# main_schematic.net
KiCad netlist of a schematic drawn in EAGLE
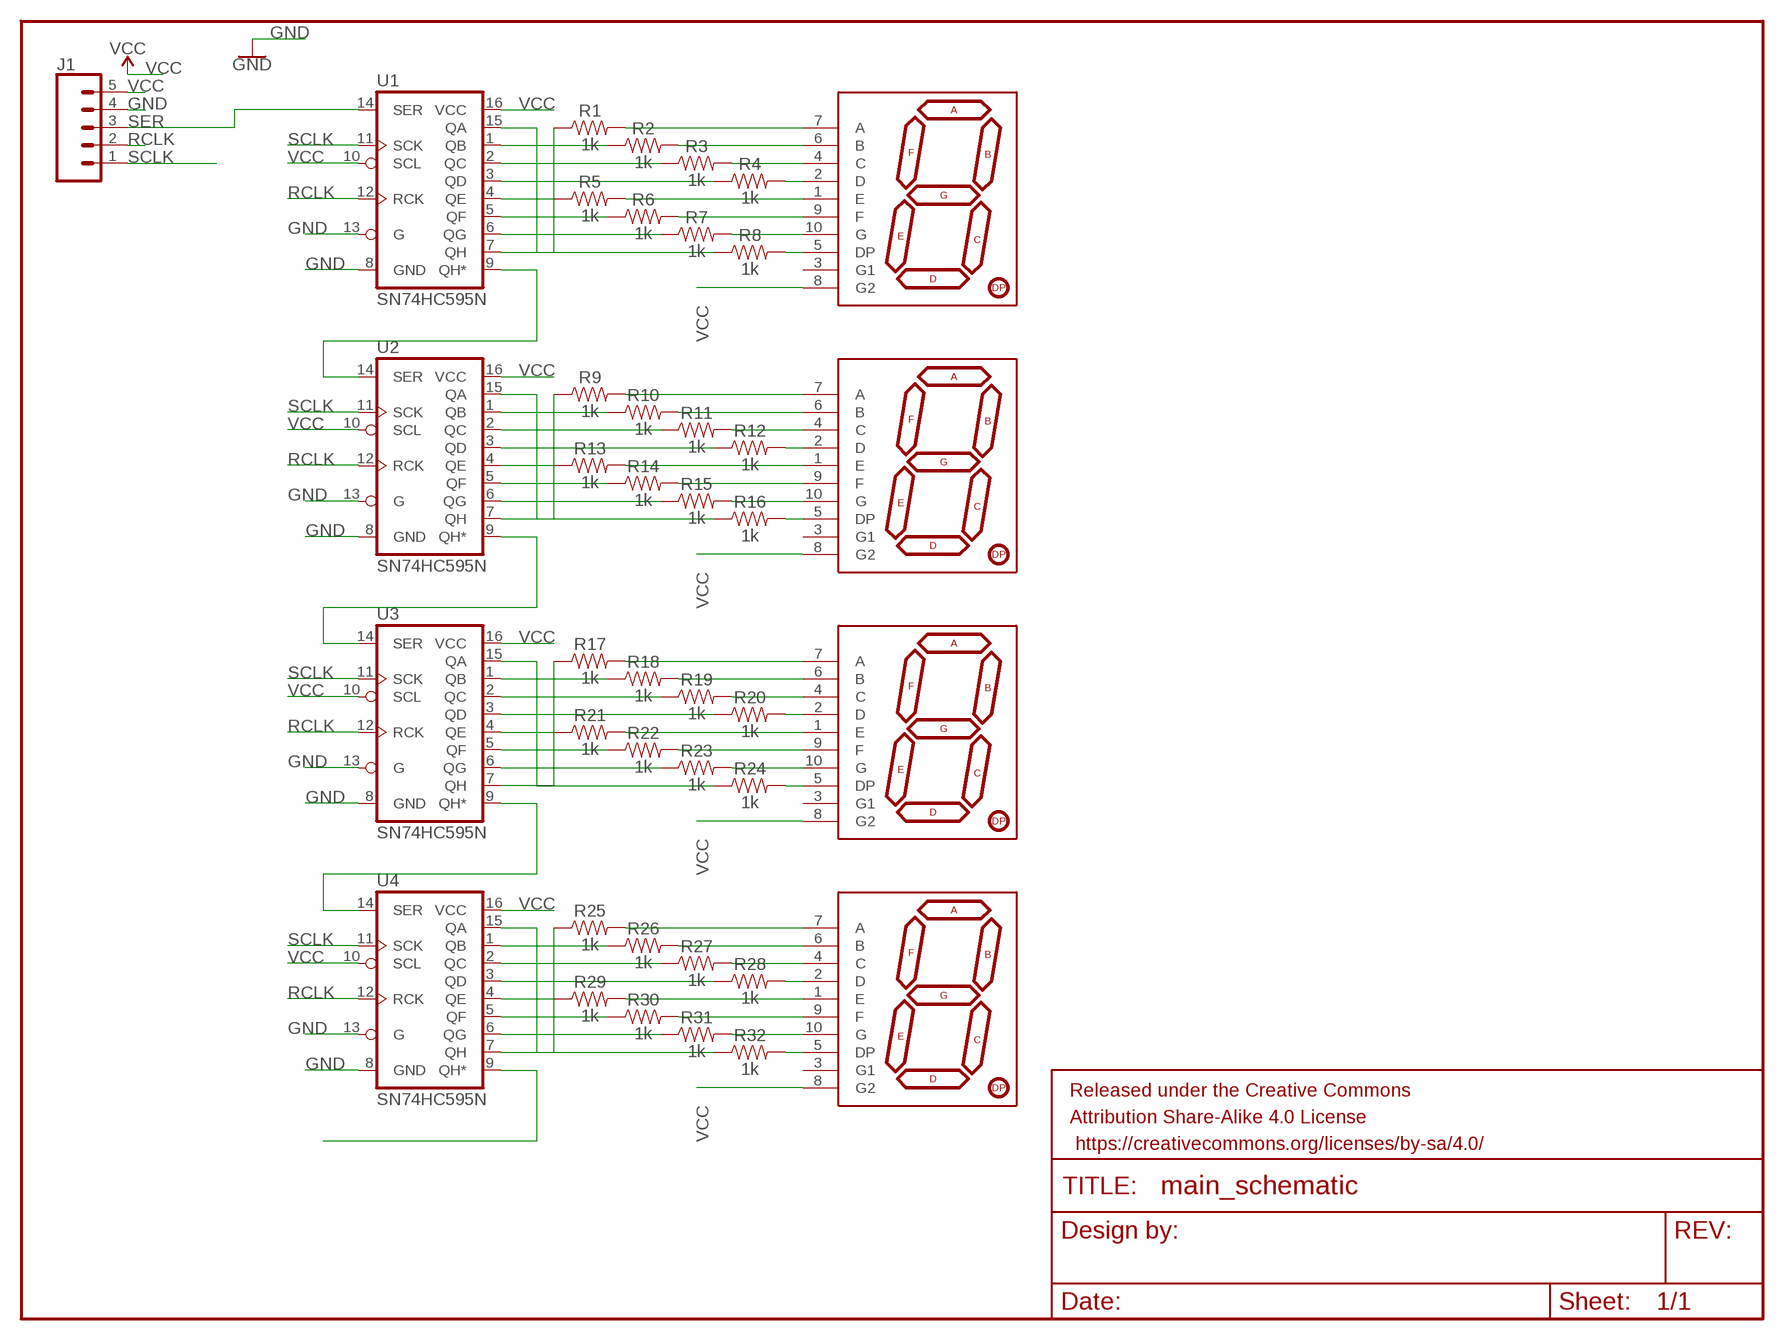
[diagram p0: schematic, sheet 1]

(export (version "E")
  (design (tool "Eeschema 10.0.6"))
  (components
    (comp (ref "FRAME1")
      (value "FRAME-LETTER")
      (footprint "eagle-import:CREATIVE_COMMONS")
      (libsource (lib "eagle-import") (part "FRAME-LETTER"))
    )
    (comp (ref "J1")
      (value "CONN_05")
      (footprint "eagle-import:1X05")
      (libsource (lib "eagle-import") (part "CONN_05"))
    )
    (comp (ref "R1")
      (value "1k")
      (footprint "eagle-import:AXIAL-0.3-KIT")
      (libsource (lib "eagle-import") (part "1KOHM-HORIZ_KIT-1/4W-5%"))
    )
    (comp (ref "R2")
      (value "1k")
      (footprint "eagle-import:AXIAL-0.3-KIT")
      (libsource (lib "eagle-import") (part "1KOHM-HORIZ_KIT-1/4W-5%"))
    )
    (comp (ref "R3")
      (value "1k")
      (footprint "eagle-import:AXIAL-0.3-KIT")
      (libsource (lib "eagle-import") (part "1KOHM-HORIZ_KIT-1/4W-5%"))
    )
    (comp (ref "R4")
      (value "1k")
      (footprint "eagle-import:AXIAL-0.3-KIT")
      (libsource (lib "eagle-import") (part "1KOHM-HORIZ_KIT-1/4W-5%"))
    )
    (comp (ref "R5")
      (value "1k")
      (footprint "eagle-import:AXIAL-0.3-KIT")
      (libsource (lib "eagle-import") (part "1KOHM-HORIZ_KIT-1/4W-5%"))
    )
    (comp (ref "R6")
      (value "1k")
      (footprint "eagle-import:AXIAL-0.3-KIT")
      (libsource (lib "eagle-import") (part "1KOHM-HORIZ_KIT-1/4W-5%"))
    )
    (comp (ref "R7")
      (value "1k")
      (footprint "eagle-import:AXIAL-0.3-KIT")
      (libsource (lib "eagle-import") (part "1KOHM-HORIZ_KIT-1/4W-5%"))
    )
    (comp (ref "R8")
      (value "1k")
      (footprint "eagle-import:AXIAL-0.3-KIT")
      (libsource (lib "eagle-import") (part "1KOHM-HORIZ_KIT-1/4W-5%"))
    )
    (comp (ref "R9")
      (value "1k")
      (footprint "eagle-import:AXIAL-0.3-KIT")
      (libsource (lib "eagle-import") (part "1KOHM-HORIZ_KIT-1/4W-5%"))
    )
    (comp (ref "R10")
      (value "1k")
      (footprint "eagle-import:AXIAL-0.3-KIT")
      (libsource (lib "eagle-import") (part "1KOHM-HORIZ_KIT-1/4W-5%"))
    )
    (comp (ref "R11")
      (value "1k")
      (footprint "eagle-import:AXIAL-0.3-KIT")
      (libsource (lib "eagle-import") (part "1KOHM-HORIZ_KIT-1/4W-5%"))
    )
    (comp (ref "R12")
      (value "1k")
      (footprint "eagle-import:AXIAL-0.3-KIT")
      (libsource (lib "eagle-import") (part "1KOHM-HORIZ_KIT-1/4W-5%"))
    )
    (comp (ref "R13")
      (value "1k")
      (footprint "eagle-import:AXIAL-0.3-KIT")
      (libsource (lib "eagle-import") (part "1KOHM-HORIZ_KIT-1/4W-5%"))
    )
    (comp (ref "R14")
      (value "1k")
      (footprint "eagle-import:AXIAL-0.3-KIT")
      (libsource (lib "eagle-import") (part "1KOHM-HORIZ_KIT-1/4W-5%"))
    )
    (comp (ref "R15")
      (value "1k")
      (footprint "eagle-import:AXIAL-0.3-KIT")
      (libsource (lib "eagle-import") (part "1KOHM-HORIZ_KIT-1/4W-5%"))
    )
    (comp (ref "R16")
      (value "1k")
      (footprint "eagle-import:AXIAL-0.3-KIT")
      (libsource (lib "eagle-import") (part "1KOHM-HORIZ_KIT-1/4W-5%"))
    )
    (comp (ref "R17")
      (value "1k")
      (footprint "eagle-import:AXIAL-0.3-KIT")
      (libsource (lib "eagle-import") (part "1KOHM-HORIZ_KIT-1/4W-5%"))
    )
    (comp (ref "R18")
      (value "1k")
      (footprint "eagle-import:AXIAL-0.3-KIT")
      (libsource (lib "eagle-import") (part "1KOHM-HORIZ_KIT-1/4W-5%"))
    )
    (comp (ref "R19")
      (value "1k")
      (footprint "eagle-import:AXIAL-0.3-KIT")
      (libsource (lib "eagle-import") (part "1KOHM-HORIZ_KIT-1/4W-5%"))
    )
    (comp (ref "R20")
      (value "1k")
      (footprint "eagle-import:AXIAL-0.3-KIT")
      (libsource (lib "eagle-import") (part "1KOHM-HORIZ_KIT-1/4W-5%"))
    )
    (comp (ref "R21")
      (value "1k")
      (footprint "eagle-import:AXIAL-0.3-KIT")
      (libsource (lib "eagle-import") (part "1KOHM-HORIZ_KIT-1/4W-5%"))
    )
    (comp (ref "R22")
      (value "1k")
      (footprint "eagle-import:AXIAL-0.3-KIT")
      (libsource (lib "eagle-import") (part "1KOHM-HORIZ_KIT-1/4W-5%"))
    )
    (comp (ref "R23")
      (value "1k")
      (footprint "eagle-import:AXIAL-0.3-KIT")
      (libsource (lib "eagle-import") (part "1KOHM-HORIZ_KIT-1/4W-5%"))
    )
    (comp (ref "R24")
      (value "1k")
      (footprint "eagle-import:AXIAL-0.3-KIT")
      (libsource (lib "eagle-import") (part "1KOHM-HORIZ_KIT-1/4W-5%"))
    )
    (comp (ref "R25")
      (value "1k")
      (footprint "eagle-import:AXIAL-0.3-KIT")
      (libsource (lib "eagle-import") (part "1KOHM-HORIZ_KIT-1/4W-5%"))
    )
    (comp (ref "R26")
      (value "1k")
      (footprint "eagle-import:AXIAL-0.3-KIT")
      (libsource (lib "eagle-import") (part "1KOHM-HORIZ_KIT-1/4W-5%"))
    )
    (comp (ref "R27")
      (value "1k")
      (footprint "eagle-import:AXIAL-0.3-KIT")
      (libsource (lib "eagle-import") (part "1KOHM-HORIZ_KIT-1/4W-5%"))
    )
    (comp (ref "R28")
      (value "1k")
      (footprint "eagle-import:AXIAL-0.3-KIT")
      (libsource (lib "eagle-import") (part "1KOHM-HORIZ_KIT-1/4W-5%"))
    )
    (comp (ref "R29")
      (value "1k")
      (footprint "eagle-import:AXIAL-0.3-KIT")
      (libsource (lib "eagle-import") (part "1KOHM-HORIZ_KIT-1/4W-5%"))
    )
    (comp (ref "R30")
      (value "1k")
      (footprint "eagle-import:AXIAL-0.3-KIT")
      (libsource (lib "eagle-import") (part "1KOHM-HORIZ_KIT-1/4W-5%"))
    )
    (comp (ref "R31")
      (value "1k")
      (footprint "eagle-import:AXIAL-0.3-KIT")
      (libsource (lib "eagle-import") (part "1KOHM-HORIZ_KIT-1/4W-5%"))
    )
    (comp (ref "R32")
      (value "1k")
      (footprint "eagle-import:AXIAL-0.3-KIT")
      (libsource (lib "eagle-import") (part "1KOHM-HORIZ_KIT-1/4W-5%"))
    )
    (comp (ref "U$1")
      (value "YSD-160AB3C-8")
      (footprint "eagle-import:7-SEGMENT-1_PTH-EZ")
      (libsource (lib "eagle-import") (part "7-SEGMENT-1DIGIT-1INCH-BLUE-EZ"))
    )
    (comp (ref "U$2")
      (value "YSD-160AB3C-8")
      (footprint "eagle-import:7-SEGMENT-1_PTH-EZ")
      (libsource (lib "eagle-import") (part "7-SEGMENT-1DIGIT-1INCH-BLUE-EZ"))
    )
    (comp (ref "U$3")
      (value "YSD-160AB3C-8")
      (footprint "eagle-import:7-SEGMENT-1_PTH-EZ")
      (libsource (lib "eagle-import") (part "7-SEGMENT-1DIGIT-1INCH-BLUE-EZ"))
    )
    (comp (ref "U$4")
      (value "YSD-160AB3C-8")
      (footprint "eagle-import:7-SEGMENT-1_PTH-EZ")
      (libsource (lib "eagle-import") (part "7-SEGMENT-1DIGIT-1INCH-BLUE-EZ"))
    )
    (comp (ref "U1")
      (value "SN74HC595N")
      (footprint "eagle-import:DIP16")
      (libsource (lib "eagle-import") (part "74595NHC"))
    )
    (comp (ref "U2")
      (value "SN74HC595N")
      (footprint "eagle-import:DIP16")
      (libsource (lib "eagle-import") (part "74595NHC"))
    )
    (comp (ref "U3")
      (value "SN74HC595N")
      (footprint "eagle-import:DIP16")
      (libsource (lib "eagle-import") (part "74595NHC"))
    )
    (comp (ref "U4")
      (value "SN74HC595N")
      (footprint "eagle-import:DIP16")
      (libsource (lib "eagle-import") (part "74595NHC"))
    )
  )
  (nets
    (net (code "1") (name "/RCLK") (class "Default")
      (node (ref "J1") (pin "2") (pinfunction "2_2") (pintype "passive"))
      (node (ref "U1") (pin "12") (pinfunction "RCK_12") (pintype "input"))
      (node (ref "U2") (pin "12") (pinfunction "RCK_12") (pintype "input"))
      (node (ref "U3") (pin "12") (pinfunction "RCK_12") (pintype "input"))
      (node (ref "U4") (pin "12") (pinfunction "RCK_12") (pintype "input"))
    )
    (net (code "2") (name "/SCLK") (class "Default")
      (node (ref "J1") (pin "1") (pinfunction "1_1") (pintype "passive"))
      (node (ref "U1") (pin "11") (pinfunction "SCK_11") (pintype "input"))
      (node (ref "U2") (pin "11") (pinfunction "SCK_11") (pintype "input"))
      (node (ref "U3") (pin "11") (pinfunction "SCK_11") (pintype "input"))
      (node (ref "U4") (pin "11") (pinfunction "SCK_11") (pintype "input"))
    )
    (net (code "3") (name "/SER") (class "Default")
      (node (ref "J1") (pin "3") (pinfunction "3_3") (pintype "passive"))
      (node (ref "U1") (pin "14") (pinfunction "SER_14") (pintype "input"))
    )
    (net (code "4") (name "GND") (class "Default")
      (node (ref "J1") (pin "4") (pinfunction "4_4") (pintype "passive"))
      (node (ref "U1") (pin "13") (pinfunction "G_13") (pintype "input"))
      (node (ref "U1") (pin "8") (pinfunction "GND_8") (pintype "power_in"))
      (node (ref "U2") (pin "13") (pinfunction "G_13") (pintype "input"))
      (node (ref "U2") (pin "8") (pinfunction "GND_8") (pintype "power_in"))
      (node (ref "U3") (pin "13") (pinfunction "G_13") (pintype "input"))
      (node (ref "U3") (pin "8") (pinfunction "GND_8") (pintype "power_in"))
      (node (ref "U4") (pin "13") (pinfunction "G_13") (pintype "input"))
      (node (ref "U4") (pin "8") (pinfunction "GND_8") (pintype "power_in"))
    )
    (net (code "5") (name "Net-(R1-1)") (class "Default")
      (node (ref "R1") (pin "P$1") (pinfunction "1_P$1") (pintype "passive"))
      (node (ref "U1") (pin "7") (pinfunction "QH_7") (pintype "tri_state"))
    )
    (net (code "6") (name "Net-(R1-2)") (class "Default")
      (node (ref "R1") (pin "P$2") (pinfunction "2_P$2") (pintype "passive"))
      (node (ref "U$1") (pin "7") (pinfunction "A_7") (pintype "bidirectional"))
    )
    (net (code "7") (name "Net-(R2-1)") (class "Default")
      (node (ref "R2") (pin "P$1") (pinfunction "1_P$1") (pintype "passive"))
      (node (ref "U1") (pin "1") (pinfunction "QB_1") (pintype "tri_state"))
    )
    (net (code "8") (name "Net-(R2-2)") (class "Default")
      (node (ref "R2") (pin "P$2") (pinfunction "2_P$2") (pintype "passive"))
      (node (ref "U$1") (pin "6") (pinfunction "B_6") (pintype "bidirectional"))
    )
    (net (code "9") (name "Net-(R3-1)") (class "Default")
      (node (ref "R3") (pin "P$1") (pinfunction "1_P$1") (pintype "passive"))
      (node (ref "U1") (pin "2") (pinfunction "QC_2") (pintype "tri_state"))
    )
    (net (code "10") (name "Net-(R3-2)") (class "Default")
      (node (ref "R3") (pin "P$2") (pinfunction "2_P$2") (pintype "passive"))
      (node (ref "U$1") (pin "4") (pinfunction "C_4") (pintype "bidirectional"))
    )
    (net (code "11") (name "Net-(R4-1)") (class "Default")
      (node (ref "R4") (pin "P$1") (pinfunction "1_P$1") (pintype "passive"))
      (node (ref "U1") (pin "3") (pinfunction "QD_3") (pintype "tri_state"))
    )
    (net (code "12") (name "Net-(R4-2)") (class "Default")
      (node (ref "R4") (pin "P$2") (pinfunction "2_P$2") (pintype "passive"))
      (node (ref "U$1") (pin "2") (pinfunction "D_2") (pintype "bidirectional"))
    )
    (net (code "13") (name "Net-(R5-1)") (class "Default")
      (node (ref "R5") (pin "P$1") (pinfunction "1_P$1") (pintype "passive"))
      (node (ref "U1") (pin "4") (pinfunction "QE_4") (pintype "tri_state"))
    )
    (net (code "14") (name "Net-(R5-2)") (class "Default")
      (node (ref "R5") (pin "P$2") (pinfunction "2_P$2") (pintype "passive"))
      (node (ref "U$1") (pin "1") (pinfunction "E_1") (pintype "bidirectional"))
    )
    (net (code "15") (name "Net-(R6-1)") (class "Default")
      (node (ref "R6") (pin "P$1") (pinfunction "1_P$1") (pintype "passive"))
      (node (ref "U1") (pin "5") (pinfunction "QF_5") (pintype "tri_state"))
    )
    (net (code "16") (name "Net-(R6-2)") (class "Default")
      (node (ref "R6") (pin "P$2") (pinfunction "2_P$2") (pintype "passive"))
      (node (ref "U$1") (pin "9") (pinfunction "F_9") (pintype "bidirectional"))
    )
    (net (code "17") (name "Net-(R7-1)") (class "Default")
      (node (ref "R7") (pin "P$1") (pinfunction "1_P$1") (pintype "passive"))
      (node (ref "U1") (pin "6") (pinfunction "QG_6") (pintype "tri_state"))
    )
    (net (code "18") (name "Net-(R7-2)") (class "Default")
      (node (ref "R7") (pin "P$2") (pinfunction "2_P$2") (pintype "passive"))
      (node (ref "U$1") (pin "10") (pinfunction "G_10") (pintype "bidirectional"))
    )
    (net (code "19") (name "Net-(R8-1)") (class "Default")
      (node (ref "R8") (pin "P$1") (pinfunction "1_P$1") (pintype "passive"))
      (node (ref "U1") (pin "15") (pinfunction "QA_15") (pintype "tri_state"))
    )
    (net (code "20") (name "Net-(R8-2)") (class "Default")
      (node (ref "R8") (pin "P$2") (pinfunction "2_P$2") (pintype "passive"))
      (node (ref "U$1") (pin "5") (pinfunction "DP_5") (pintype "bidirectional"))
    )
    (net (code "21") (name "Net-(R9-1)") (class "Default")
      (node (ref "R9") (pin "P$1") (pinfunction "1_P$1") (pintype "passive"))
      (node (ref "U2") (pin "7") (pinfunction "QH_7") (pintype "tri_state"))
    )
    (net (code "22") (name "Net-(R9-2)") (class "Default")
      (node (ref "R9") (pin "P$2") (pinfunction "2_P$2") (pintype "passive"))
      (node (ref "U$2") (pin "7") (pinfunction "A_7") (pintype "bidirectional"))
    )
    (net (code "23") (name "Net-(R10-1)") (class "Default")
      (node (ref "R10") (pin "P$1") (pinfunction "1_P$1") (pintype "passive"))
      (node (ref "U2") (pin "1") (pinfunction "QB_1") (pintype "tri_state"))
    )
    (net (code "24") (name "Net-(R10-2)") (class "Default")
      (node (ref "R10") (pin "P$2") (pinfunction "2_P$2") (pintype "passive"))
      (node (ref "U$2") (pin "6") (pinfunction "B_6") (pintype "bidirectional"))
    )
    (net (code "25") (name "Net-(R11-1)") (class "Default")
      (node (ref "R11") (pin "P$1") (pinfunction "1_P$1") (pintype "passive"))
      (node (ref "U2") (pin "2") (pinfunction "QC_2") (pintype "tri_state"))
    )
    (net (code "26") (name "Net-(R11-2)") (class "Default")
      (node (ref "R11") (pin "P$2") (pinfunction "2_P$2") (pintype "passive"))
      (node (ref "U$2") (pin "4") (pinfunction "C_4") (pintype "bidirectional"))
    )
    (net (code "27") (name "Net-(R12-1)") (class "Default")
      (node (ref "R12") (pin "P$1") (pinfunction "1_P$1") (pintype "passive"))
      (node (ref "U2") (pin "3") (pinfunction "QD_3") (pintype "tri_state"))
    )
    (net (code "28") (name "Net-(R12-2)") (class "Default")
      (node (ref "R12") (pin "P$2") (pinfunction "2_P$2") (pintype "passive"))
      (node (ref "U$2") (pin "2") (pinfunction "D_2") (pintype "bidirectional"))
    )
    (net (code "29") (name "Net-(R13-1)") (class "Default")
      (node (ref "R13") (pin "P$1") (pinfunction "1_P$1") (pintype "passive"))
      (node (ref "U2") (pin "4") (pinfunction "QE_4") (pintype "tri_state"))
    )
    (net (code "30") (name "Net-(R13-2)") (class "Default")
      (node (ref "R13") (pin "P$2") (pinfunction "2_P$2") (pintype "passive"))
      (node (ref "U$2") (pin "1") (pinfunction "E_1") (pintype "bidirectional"))
    )
    (net (code "31") (name "Net-(R14-1)") (class "Default")
      (node (ref "R14") (pin "P$1") (pinfunction "1_P$1") (pintype "passive"))
      (node (ref "U2") (pin "5") (pinfunction "QF_5") (pintype "tri_state"))
    )
    (net (code "32") (name "Net-(R14-2)") (class "Default")
      (node (ref "R14") (pin "P$2") (pinfunction "2_P$2") (pintype "passive"))
      (node (ref "U$2") (pin "9") (pinfunction "F_9") (pintype "bidirectional"))
    )
    (net (code "33") (name "Net-(R15-1)") (class "Default")
      (node (ref "R15") (pin "P$1") (pinfunction "1_P$1") (pintype "passive"))
      (node (ref "U2") (pin "6") (pinfunction "QG_6") (pintype "tri_state"))
    )
    (net (code "34") (name "Net-(R15-2)") (class "Default")
      (node (ref "R15") (pin "P$2") (pinfunction "2_P$2") (pintype "passive"))
      (node (ref "U$2") (pin "10") (pinfunction "G_10") (pintype "bidirectional"))
    )
    (net (code "35") (name "Net-(R16-1)") (class "Default")
      (node (ref "R16") (pin "P$1") (pinfunction "1_P$1") (pintype "passive"))
      (node (ref "U2") (pin "15") (pinfunction "QA_15") (pintype "tri_state"))
    )
    (net (code "36") (name "Net-(R16-2)") (class "Default")
      (node (ref "R16") (pin "P$2") (pinfunction "2_P$2") (pintype "passive"))
      (node (ref "U$2") (pin "5") (pinfunction "DP_5") (pintype "bidirectional"))
    )
    (net (code "37") (name "Net-(R17-1)") (class "Default")
      (node (ref "R17") (pin "P$1") (pinfunction "1_P$1") (pintype "passive"))
      (node (ref "U3") (pin "7") (pinfunction "QH_7") (pintype "tri_state"))
    )
    (net (code "38") (name "Net-(R17-2)") (class "Default")
      (node (ref "R17") (pin "P$2") (pinfunction "2_P$2") (pintype "passive"))
      (node (ref "U$3") (pin "7") (pinfunction "A_7") (pintype "bidirectional"))
    )
    (net (code "39") (name "Net-(R18-1)") (class "Default")
      (node (ref "R18") (pin "P$1") (pinfunction "1_P$1") (pintype "passive"))
      (node (ref "U3") (pin "1") (pinfunction "QB_1") (pintype "tri_state"))
    )
    (net (code "40") (name "Net-(R18-2)") (class "Default")
      (node (ref "R18") (pin "P$2") (pinfunction "2_P$2") (pintype "passive"))
      (node (ref "U$3") (pin "6") (pinfunction "B_6") (pintype "bidirectional"))
    )
    (net (code "41") (name "Net-(R19-1)") (class "Default")
      (node (ref "R19") (pin "P$1") (pinfunction "1_P$1") (pintype "passive"))
      (node (ref "U3") (pin "2") (pinfunction "QC_2") (pintype "tri_state"))
    )
    (net (code "42") (name "Net-(R19-2)") (class "Default")
      (node (ref "R19") (pin "P$2") (pinfunction "2_P$2") (pintype "passive"))
      (node (ref "U$3") (pin "4") (pinfunction "C_4") (pintype "bidirectional"))
    )
    (net (code "43") (name "Net-(R20-1)") (class "Default")
      (node (ref "R20") (pin "P$1") (pinfunction "1_P$1") (pintype "passive"))
      (node (ref "U3") (pin "3") (pinfunction "QD_3") (pintype "tri_state"))
    )
    (net (code "44") (name "Net-(R20-2)") (class "Default")
      (node (ref "R20") (pin "P$2") (pinfunction "2_P$2") (pintype "passive"))
      (node (ref "U$3") (pin "2") (pinfunction "D_2") (pintype "bidirectional"))
    )
    (net (code "45") (name "Net-(R21-1)") (class "Default")
      (node (ref "R21") (pin "P$1") (pinfunction "1_P$1") (pintype "passive"))
      (node (ref "U3") (pin "4") (pinfunction "QE_4") (pintype "tri_state"))
    )
    (net (code "46") (name "Net-(R21-2)") (class "Default")
      (node (ref "R21") (pin "P$2") (pinfunction "2_P$2") (pintype "passive"))
      (node (ref "U$3") (pin "1") (pinfunction "E_1") (pintype "bidirectional"))
    )
    (net (code "47") (name "Net-(R22-1)") (class "Default")
      (node (ref "R22") (pin "P$1") (pinfunction "1_P$1") (pintype "passive"))
      (node (ref "U3") (pin "5") (pinfunction "QF_5") (pintype "tri_state"))
    )
    (net (code "48") (name "Net-(R22-2)") (class "Default")
      (node (ref "R22") (pin "P$2") (pinfunction "2_P$2") (pintype "passive"))
      (node (ref "U$3") (pin "9") (pinfunction "F_9") (pintype "bidirectional"))
    )
    (net (code "49") (name "Net-(R23-1)") (class "Default")
      (node (ref "R23") (pin "P$1") (pinfunction "1_P$1") (pintype "passive"))
      (node (ref "U3") (pin "6") (pinfunction "QG_6") (pintype "tri_state"))
    )
    (net (code "50") (name "Net-(R23-2)") (class "Default")
      (node (ref "R23") (pin "P$2") (pinfunction "2_P$2") (pintype "passive"))
      (node (ref "U$3") (pin "10") (pinfunction "G_10") (pintype "bidirectional"))
    )
    (net (code "51") (name "Net-(R24-1)") (class "Default")
      (node (ref "R24") (pin "P$1") (pinfunction "1_P$1") (pintype "passive"))
      (node (ref "U3") (pin "15") (pinfunction "QA_15") (pintype "tri_state"))
    )
    (net (code "52") (name "Net-(R24-2)") (class "Default")
      (node (ref "R24") (pin "P$2") (pinfunction "2_P$2") (pintype "passive"))
      (node (ref "U$3") (pin "5") (pinfunction "DP_5") (pintype "bidirectional"))
    )
    (net (code "53") (name "Net-(R25-1)") (class "Default")
      (node (ref "R25") (pin "P$1") (pinfunction "1_P$1") (pintype "passive"))
      (node (ref "U4") (pin "7") (pinfunction "QH_7") (pintype "tri_state"))
    )
    (net (code "54") (name "Net-(R25-2)") (class "Default")
      (node (ref "R25") (pin "P$2") (pinfunction "2_P$2") (pintype "passive"))
      (node (ref "U$4") (pin "7") (pinfunction "A_7") (pintype "bidirectional"))
    )
    (net (code "55") (name "Net-(R26-1)") (class "Default")
      (node (ref "R26") (pin "P$1") (pinfunction "1_P$1") (pintype "passive"))
      (node (ref "U4") (pin "1") (pinfunction "QB_1") (pintype "tri_state"))
    )
    (net (code "56") (name "Net-(R26-2)") (class "Default")
      (node (ref "R26") (pin "P$2") (pinfunction "2_P$2") (pintype "passive"))
      (node (ref "U$4") (pin "6") (pinfunction "B_6") (pintype "bidirectional"))
    )
    (net (code "57") (name "Net-(R27-1)") (class "Default")
      (node (ref "R27") (pin "P$1") (pinfunction "1_P$1") (pintype "passive"))
      (node (ref "U4") (pin "2") (pinfunction "QC_2") (pintype "tri_state"))
    )
    (net (code "58") (name "Net-(R27-2)") (class "Default")
      (node (ref "R27") (pin "P$2") (pinfunction "2_P$2") (pintype "passive"))
      (node (ref "U$4") (pin "4") (pinfunction "C_4") (pintype "bidirectional"))
    )
    (net (code "59") (name "Net-(R28-1)") (class "Default")
      (node (ref "R28") (pin "P$1") (pinfunction "1_P$1") (pintype "passive"))
      (node (ref "U4") (pin "3") (pinfunction "QD_3") (pintype "tri_state"))
    )
    (net (code "60") (name "Net-(R28-2)") (class "Default")
      (node (ref "R28") (pin "P$2") (pinfunction "2_P$2") (pintype "passive"))
      (node (ref "U$4") (pin "2") (pinfunction "D_2") (pintype "bidirectional"))
    )
    (net (code "61") (name "Net-(R29-1)") (class "Default")
      (node (ref "R29") (pin "P$1") (pinfunction "1_P$1") (pintype "passive"))
      (node (ref "U4") (pin "4") (pinfunction "QE_4") (pintype "tri_state"))
    )
    (net (code "62") (name "Net-(R29-2)") (class "Default")
      (node (ref "R29") (pin "P$2") (pinfunction "2_P$2") (pintype "passive"))
      (node (ref "U$4") (pin "1") (pinfunction "E_1") (pintype "bidirectional"))
    )
    (net (code "63") (name "Net-(R30-1)") (class "Default")
      (node (ref "R30") (pin "P$1") (pinfunction "1_P$1") (pintype "passive"))
      (node (ref "U4") (pin "5") (pinfunction "QF_5") (pintype "tri_state"))
    )
    (net (code "64") (name "Net-(R30-2)") (class "Default")
      (node (ref "R30") (pin "P$2") (pinfunction "2_P$2") (pintype "passive"))
      (node (ref "U$4") (pin "9") (pinfunction "F_9") (pintype "bidirectional"))
    )
    (net (code "65") (name "Net-(R31-1)") (class "Default")
      (node (ref "R31") (pin "P$1") (pinfunction "1_P$1") (pintype "passive"))
      (node (ref "U4") (pin "6") (pinfunction "QG_6") (pintype "tri_state"))
    )
    (net (code "66") (name "Net-(R31-2)") (class "Default")
      (node (ref "R31") (pin "P$2") (pinfunction "2_P$2") (pintype "passive"))
      (node (ref "U$4") (pin "10") (pinfunction "G_10") (pintype "bidirectional"))
    )
    (net (code "67") (name "Net-(R32-1)") (class "Default")
      (node (ref "R32") (pin "P$1") (pinfunction "1_P$1") (pintype "passive"))
      (node (ref "U4") (pin "15") (pinfunction "QA_15") (pintype "tri_state"))
    )
    (net (code "68") (name "Net-(R32-2)") (class "Default")
      (node (ref "R32") (pin "P$2") (pinfunction "2_P$2") (pintype "passive"))
      (node (ref "U$4") (pin "5") (pinfunction "DP_5") (pintype "bidirectional"))
    )
    (net (code "69") (name "Net-(U1-QH*)") (class "Default")
      (node (ref "U1") (pin "9") (pinfunction "QH*_9") (pintype "tri_state"))
      (node (ref "U2") (pin "14") (pinfunction "SER_14") (pintype "input"))
    )
    (net (code "70") (name "Net-(U2-QH*)") (class "Default")
      (node (ref "U2") (pin "9") (pinfunction "QH*_9") (pintype "tri_state"))
      (node (ref "U3") (pin "14") (pinfunction "SER_14") (pintype "input"))
    )
    (net (code "71") (name "Net-(U3-QH*)") (class "Default")
      (node (ref "U3") (pin "9") (pinfunction "QH*_9") (pintype "tri_state"))
      (node (ref "U4") (pin "14") (pinfunction "SER_14") (pintype "input"))
    )
    (net (code "72") (name "VCC") (class "Default")
      (node (ref "J1") (pin "5") (pinfunction "5_5") (pintype "passive"))
      (node (ref "U$1") (pin "8") (pinfunction "G2_8") (pintype "bidirectional"))
      (node (ref "U$2") (pin "8") (pinfunction "G2_8") (pintype "bidirectional"))
      (node (ref "U$3") (pin "8") (pinfunction "G2_8") (pintype "bidirectional"))
      (node (ref "U$4") (pin "8") (pinfunction "G2_8") (pintype "bidirectional"))
      (node (ref "U1") (pin "10") (pinfunction "SCL_10") (pintype "input"))
      (node (ref "U1") (pin "16") (pinfunction "VCC_16") (pintype "power_in"))
      (node (ref "U2") (pin "10") (pinfunction "SCL_10") (pintype "input"))
      (node (ref "U2") (pin "16") (pinfunction "VCC_16") (pintype "power_in"))
      (node (ref "U3") (pin "10") (pinfunction "SCL_10") (pintype "input"))
      (node (ref "U3") (pin "16") (pinfunction "VCC_16") (pintype "power_in"))
      (node (ref "U4") (pin "10") (pinfunction "SCL_10") (pintype "input"))
      (node (ref "U4") (pin "16") (pinfunction "VCC_16") (pintype "power_in"))
    )
    (net (code "73") (name "unconnected-(U$1-G1-Pad3)") (class "Default")
      (node (ref "U$1") (pin "3") (pinfunction "G1_3") (pintype "bidirectional"))
    )
    (net (code "74") (name "unconnected-(U$2-G1-Pad3)") (class "Default")
      (node (ref "U$2") (pin "3") (pinfunction "G1_3") (pintype "bidirectional"))
    )
    (net (code "75") (name "unconnected-(U$3-G1-Pad3)") (class "Default")
      (node (ref "U$3") (pin "3") (pinfunction "G1_3") (pintype "bidirectional"))
    )
    (net (code "76") (name "unconnected-(U$4-G1-Pad3)") (class "Default")
      (node (ref "U$4") (pin "3") (pinfunction "G1_3") (pintype "bidirectional"))
    )
    (net (code "77") (name "unconnected-(U4-QH*-Pad9)") (class "Default")
      (node (ref "U4") (pin "9") (pinfunction "QH*_9") (pintype "tri_state"))
    )
  )
)
